# Sheet_1_2025-10-18.net
KiCad netlist of a schematic drawn in Altium Designer
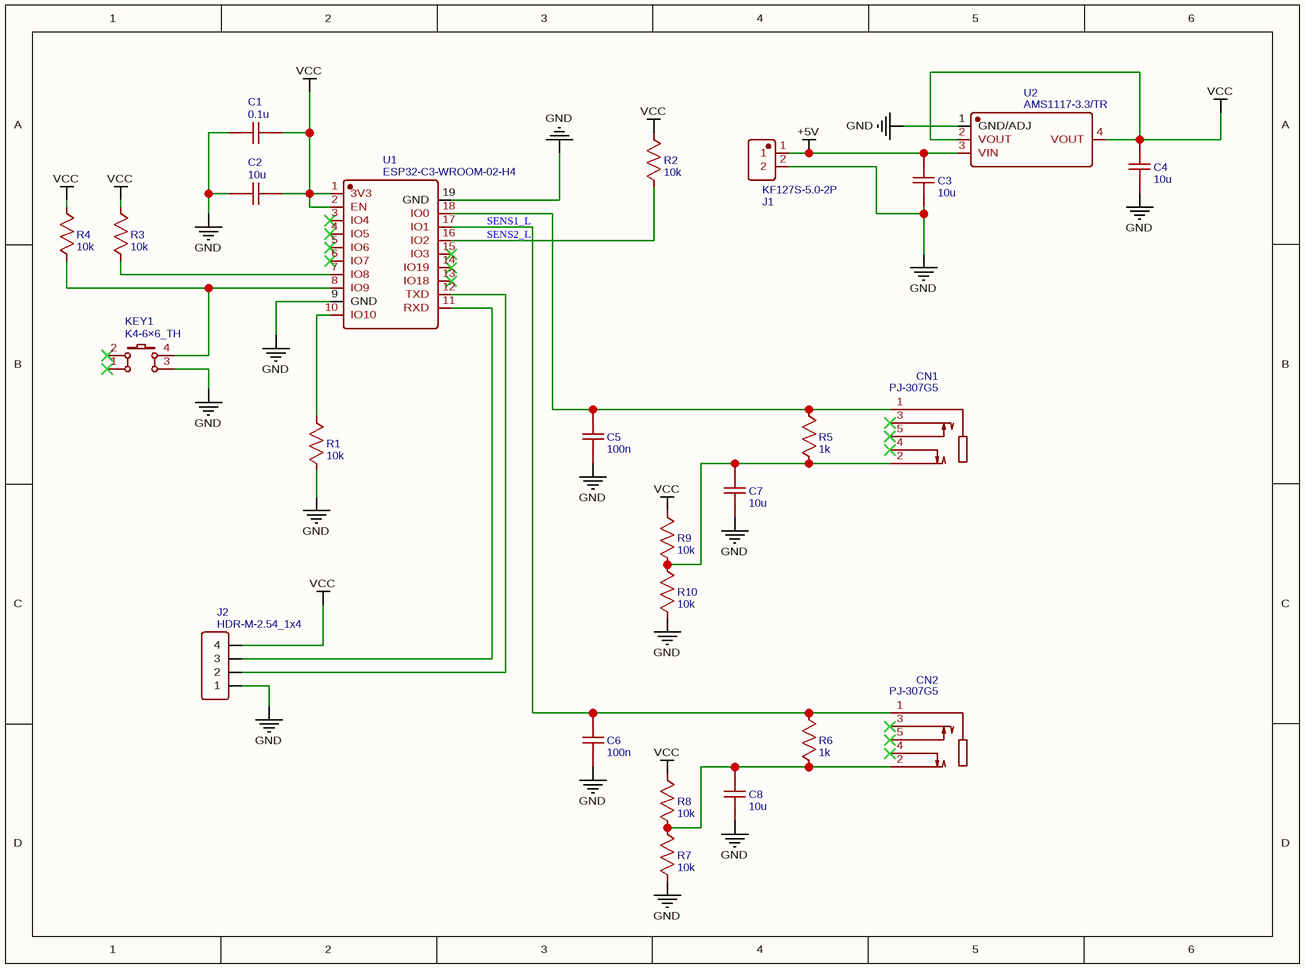
[diagram p0: Sheet_1_2025-10-18.schdoc]

(export (version "E")
  (design (tool "Eeschema 10.0.6"))
  (components
    (comp (ref "C1")
      (value "0.1u")
      (fields (field (name "CONTRIBUTOR") "LCEDA_Lib"))
      (libsource (lib "altium-import") (part "root_0_0.1u_"))
    )
    (comp (ref "C2")
      (value "10u")
      (fields (field (name "CONTRIBUTOR") "LCEDA_Lib"))
      (libsource (lib "altium-import") (part "root_0_10u_"))
    )
    (comp (ref "C3")
      (value "10u")
      (fields (field (name "CONTRIBUTOR") "LCEDA_Lib"))
      (libsource (lib "altium-import") (part "root_1_10u_"))
    )
    (comp (ref "C4")
      (value "10u")
      (fields (field (name "CONTRIBUTOR") "LCEDA_Lib"))
      (libsource (lib "altium-import") (part "root_1_10u_"))
    )
    (comp (ref "C5")
      (value "100n")
      (fields (field (name "CONTRIBUTOR") "LCEDA_Lib"))
      (libsource (lib "altium-import") (part "root_1_100n_"))
    )
    (comp (ref "C6")
      (value "100n")
      (fields (field (name "CONTRIBUTOR") "LCEDA_Lib"))
      (libsource (lib "altium-import") (part "root_1_100n_"))
    )
    (comp (ref "C7")
      (value "10u")
      (fields (field (name "CONTRIBUTOR") "LCEDA_Lib"))
      (libsource (lib "altium-import") (part "root_1_10u_"))
    )
    (comp (ref "C8")
      (value "10u")
      (fields (field (name "CONTRIBUTOR") "LCEDA_Lib"))
      (libsource (lib "altium-import") (part "root_1_10u_"))
    )
    (comp (ref "CN1")
      (value "PJ-307G5")
      (fields (field (name "MANUFACTURER") "XKB Connectivity(中国星坤)") (field (name "CONTRIBUTOR") "LCSC"))
      (libsource (lib "altium-import") (part "root_0_PJ-307G5_"))
    )
    (comp (ref "CN2")
      (value "PJ-307G5")
      (fields (field (name "MANUFACTURER") "XKB Connectivity(中国星坤)") (field (name "CONTRIBUTOR") "LCSC"))
      (libsource (lib "altium-import") (part "root_0_PJ-307G5_"))
    )
    (comp (ref "J1")
      (value "KF127S-5.0-2P")
      (fields (field (name "MANUFACTURER") "KEFA(科发)") (field (name "CONTRIBUTOR") "lcsc"))
      (libsource (lib "altium-import") (part "root_2_KF127S-5.0-2P_"))
    )
    (comp (ref "J2")
      (value "HDR-M-2.54_1x4")
      (fields (field (name "CONTRIBUTOR") "LCEDA_Lib"))
      (libsource (lib "altium-import") (part "root_2_HDR-M-2.54_1x4_"))
    )
    (comp (ref "KEY1")
      (value "K4-6×6_TH")
      (fields
        (field (name "MANUFACTURER") "韩国韩荣")
        (field (name "MANUFACTURER PART") "K2-1102DP-E4SW-04")
        (field (name "CONTRIBUTOR") "LCEDA_Lib")
      )
      (libsource (lib "altium-import") (part "root_0_K4-6×6_TH_"))
    )
    (comp (ref "R1")
      (value "10k")
      (fields (field (name "CONTRIBUTOR") "LCEDA_Lib"))
      (libsource (lib "altium-import") (part "root_1_10k_"))
    )
    (comp (ref "R2")
      (value "10k")
      (fields (field (name "CONTRIBUTOR") "LCEDA_Lib"))
      (libsource (lib "altium-import") (part "root_1_10k_"))
    )
    (comp (ref "R3")
      (value "10k")
      (fields (field (name "CONTRIBUTOR") "LCEDA_Lib"))
      (libsource (lib "altium-import") (part "root_1_10k_"))
    )
    (comp (ref "R4")
      (value "10k")
      (fields (field (name "CONTRIBUTOR") "LCEDA_Lib"))
      (libsource (lib "altium-import") (part "root_1_10k_"))
    )
    (comp (ref "R5")
      (value "1k")
      (fields (field (name "CONTRIBUTOR") "LCEDA_Lib"))
      (libsource (lib "altium-import") (part "root_1_1k_"))
    )
    (comp (ref "R6")
      (value "1k")
      (fields (field (name "CONTRIBUTOR") "LCEDA_Lib"))
      (libsource (lib "altium-import") (part "root_1_1k_"))
    )
    (comp (ref "R7")
      (value "10k")
      (fields (field (name "CONTRIBUTOR") "LCEDA_Lib"))
      (libsource (lib "altium-import") (part "root_1_10k_"))
    )
    (comp (ref "R8")
      (value "10k")
      (fields (field (name "CONTRIBUTOR") "LCEDA_Lib"))
      (libsource (lib "altium-import") (part "root_1_10k_"))
    )
    (comp (ref "R9")
      (value "10k")
      (fields (field (name "CONTRIBUTOR") "LCEDA_Lib"))
      (libsource (lib "altium-import") (part "root_1_10k_"))
    )
    (comp (ref "R10")
      (value "10k")
      (fields (field (name "CONTRIBUTOR") "LCEDA_Lib"))
      (libsource (lib "altium-import") (part "root_1_10k_"))
    )
    (comp (ref "U1")
      (value "ESP32-C3-WROOM-02-H4")
      (fields (field (name "MANUFACTURER") "ESPRESSIF(乐鑫)") (field (name "CONTRIBUTOR") "LCSC"))
      (libsource (lib "altium-import") (part "root_0_ESP32-C3-WROOM-02-H4_"))
    )
    (comp (ref "U2")
      (value "AMS1117-3.3/TR")
      (fields (field (name "MANUFACTURER") "HGSEMI(华冠)") (field (name "CONTRIBUTOR") "lcsc"))
      (libsource (lib "altium-import") (part "root_0_AMS1117-3.3/TR_"))
    )
  )
  (nets
    (net (code "1") (name "+5V") (class "Default")
      (node (ref "C3") (pin "2") (pinfunction "2_2") (pintype "passive"))
      (node (ref "J1") (pin "1") (pinfunction "1_1") (pintype "passive"))
      (node (ref "U2") (pin "3") (pinfunction "VIN_3") (pintype "passive"))
    )
    (net (code "2") (name "/SENS1_L") (class "Default")
      (node (ref "C5") (pin "2") (pinfunction "2_2") (pintype "passive"))
      (node (ref "CN1") (pin "1") (pinfunction "1_1") (pintype "passive"))
      (node (ref "R5") (pin "2") (pinfunction "2_2") (pintype "passive"))
      (node (ref "U1") (pin "18") (pinfunction "IO0_18") (pintype "passive"))
    )
    (net (code "3") (name "/SENS2_L") (class "Default")
      (node (ref "C6") (pin "2") (pinfunction "2_2") (pintype "passive"))
      (node (ref "CN2") (pin "1") (pinfunction "1_1") (pintype "passive"))
      (node (ref "R6") (pin "2") (pinfunction "2_2") (pintype "passive"))
      (node (ref "U1") (pin "17") (pinfunction "IO1_17") (pintype "passive"))
    )
    (net (code "4") (name "GND") (class "Default")
      (node (ref "C1") (pin "1") (pinfunction "1_1") (pintype "passive"))
      (node (ref "C2") (pin "1") (pinfunction "1_1") (pintype "passive"))
      (node (ref "C3") (pin "1") (pinfunction "1_1") (pintype "passive"))
      (node (ref "C4") (pin "1") (pinfunction "1_1") (pintype "passive"))
      (node (ref "C5") (pin "1") (pinfunction "1_1") (pintype "passive"))
      (node (ref "C6") (pin "1") (pinfunction "1_1") (pintype "passive"))
      (node (ref "C7") (pin "1") (pinfunction "1_1") (pintype "passive"))
      (node (ref "C8") (pin "1") (pinfunction "1_1") (pintype "passive"))
      (node (ref "J1") (pin "2") (pinfunction "2_2") (pintype "passive"))
      (node (ref "J2") (pin "1") (pinfunction "1_1") (pintype "passive"))
      (node (ref "KEY1") (pin "3") (pinfunction "3_3") (pintype "passive"))
      (node (ref "R1") (pin "1") (pinfunction "1_1") (pintype "passive"))
      (node (ref "R10") (pin "1") (pinfunction "1_1") (pintype "passive"))
      (node (ref "R7") (pin "1") (pinfunction "1_1") (pintype "passive"))
      (node (ref "U1") (pin "19") (pinfunction "GND_19") (pintype "passive"))
      (node (ref "U1") (pin "9") (pinfunction "GND_9") (pintype "passive"))
      (node (ref "U2") (pin "1") (pinfunction "GND/ADJ_1") (pintype "passive"))
    )
    (net (code "5") (name "Net-(C7-Pad2)") (class "Default")
      (node (ref "C7") (pin "2") (pinfunction "2_2") (pintype "passive"))
      (node (ref "CN1") (pin "2") (pinfunction "2_2") (pintype "passive"))
      (node (ref "R10") (pin "2") (pinfunction "2_2") (pintype "passive"))
      (node (ref "R5") (pin "1") (pinfunction "1_1") (pintype "passive"))
      (node (ref "R9") (pin "1") (pinfunction "1_1") (pintype "passive"))
    )
    (net (code "6") (name "Net-(C8-Pad2)") (class "Default")
      (node (ref "C8") (pin "2") (pinfunction "2_2") (pintype "passive"))
      (node (ref "CN2") (pin "2") (pinfunction "2_2") (pintype "passive"))
      (node (ref "R6") (pin "1") (pinfunction "1_1") (pintype "passive"))
      (node (ref "R7") (pin "2") (pinfunction "2_2") (pintype "passive"))
      (node (ref "R8") (pin "1") (pinfunction "1_1") (pintype "passive"))
    )
    (net (code "7") (name "Net-(U1-IO2)") (class "Default")
      (node (ref "R2") (pin "1") (pinfunction "1_1") (pintype "passive"))
      (node (ref "U1") (pin "16") (pinfunction "IO2_16") (pintype "passive"))
    )
    (net (code "8") (name "Net-(U1-IO8)") (class "Default")
      (node (ref "R3") (pin "1") (pinfunction "1_1") (pintype "passive"))
      (node (ref "U1") (pin "7") (pinfunction "IO8_7") (pintype "passive"))
    )
    (net (code "9") (name "Net-(U1-IO9)") (class "Default")
      (node (ref "KEY1") (pin "4") (pinfunction "4_4") (pintype "passive"))
      (node (ref "R4") (pin "1") (pinfunction "1_1") (pintype "passive"))
      (node (ref "U1") (pin "8") (pinfunction "IO9_8") (pintype "passive"))
    )
    (net (code "10") (name "Net-(U1-IO10)") (class "Default")
      (node (ref "R1") (pin "2") (pinfunction "2_2") (pintype "passive"))
      (node (ref "U1") (pin "10") (pinfunction "IO10_10") (pintype "passive"))
    )
    (net (code "11") (name "Net-(U1-RXD)") (class "Default")
      (node (ref "J2") (pin "3") (pinfunction "3_3") (pintype "passive"))
      (node (ref "U1") (pin "11") (pinfunction "RXD_11") (pintype "passive"))
    )
    (net (code "12") (name "Net-(U1-TXD)") (class "Default")
      (node (ref "J2") (pin "2") (pinfunction "2_2") (pintype "passive"))
      (node (ref "U1") (pin "12") (pinfunction "TXD_12") (pintype "passive"))
    )
    (net (code "13") (name "VCC") (class "Default")
      (node (ref "C1") (pin "2") (pinfunction "2_2") (pintype "passive"))
      (node (ref "C2") (pin "2") (pinfunction "2_2") (pintype "passive"))
      (node (ref "C4") (pin "2") (pinfunction "2_2") (pintype "passive"))
      (node (ref "J2") (pin "4") (pinfunction "4_4") (pintype "passive"))
      (node (ref "R2") (pin "2") (pinfunction "2_2") (pintype "passive"))
      (node (ref "R3") (pin "2") (pinfunction "2_2") (pintype "passive"))
      (node (ref "R4") (pin "2") (pinfunction "2_2") (pintype "passive"))
      (node (ref "R8") (pin "2") (pinfunction "2_2") (pintype "passive"))
      (node (ref "R9") (pin "2") (pinfunction "2_2") (pintype "passive"))
      (node (ref "U1") (pin "1") (pinfunction "3V3_1") (pintype "passive"))
      (node (ref "U1") (pin "2") (pinfunction "EN_2") (pintype "passive"))
      (node (ref "U2") (pin "2") (pinfunction "VOUT_2") (pintype "passive"))
      (node (ref "U2") (pin "4") (pinfunction "VOUT_4") (pintype "passive"))
    )
    (net (code "14") (name "unconnected-(CN1-Pad3)") (class "Default")
      (node (ref "CN1") (pin "3") (pinfunction "3_3") (pintype "passive+no_connect"))
    )
    (net (code "15") (name "unconnected-(CN1-Pad4)") (class "Default")
      (node (ref "CN1") (pin "4") (pinfunction "4_4") (pintype "passive+no_connect"))
    )
    (net (code "16") (name "unconnected-(CN1-Pad5)") (class "Default")
      (node (ref "CN1") (pin "5") (pinfunction "5_5") (pintype "passive+no_connect"))
    )
    (net (code "17") (name "unconnected-(CN2-Pad3)") (class "Default")
      (node (ref "CN2") (pin "3") (pinfunction "3_3") (pintype "passive+no_connect"))
    )
    (net (code "18") (name "unconnected-(CN2-Pad4)") (class "Default")
      (node (ref "CN2") (pin "4") (pinfunction "4_4") (pintype "passive+no_connect"))
    )
    (net (code "19") (name "unconnected-(CN2-Pad5)") (class "Default")
      (node (ref "CN2") (pin "5") (pinfunction "5_5") (pintype "passive+no_connect"))
    )
    (net (code "20") (name "unconnected-(KEY1-Pad1)") (class "Default")
      (node (ref "KEY1") (pin "1") (pinfunction "1_1") (pintype "passive+no_connect"))
    )
    (net (code "21") (name "unconnected-(KEY1-Pad2)") (class "Default")
      (node (ref "KEY1") (pin "2") (pinfunction "2_2") (pintype "passive+no_connect"))
    )
    (net (code "22") (name "unconnected-(U1-IO3-Pad15)") (class "Default")
      (node (ref "U1") (pin "15") (pinfunction "IO3_15") (pintype "passive+no_connect"))
    )
    (net (code "23") (name "unconnected-(U1-IO4-Pad3)") (class "Default")
      (node (ref "U1") (pin "3") (pinfunction "IO4_3") (pintype "passive+no_connect"))
    )
    (net (code "24") (name "unconnected-(U1-IO5-Pad4)") (class "Default")
      (node (ref "U1") (pin "4") (pinfunction "IO5_4") (pintype "passive+no_connect"))
    )
    (net (code "25") (name "unconnected-(U1-IO6-Pad5)") (class "Default")
      (node (ref "U1") (pin "5") (pinfunction "IO6_5") (pintype "passive+no_connect"))
    )
    (net (code "26") (name "unconnected-(U1-IO7-Pad6)") (class "Default")
      (node (ref "U1") (pin "6") (pinfunction "IO7_6") (pintype "passive+no_connect"))
    )
    (net (code "27") (name "unconnected-(U1-IO18-Pad13)") (class "Default")
      (node (ref "U1") (pin "13") (pinfunction "IO18_13") (pintype "passive+no_connect"))
    )
    (net (code "28") (name "unconnected-(U1-IO19-Pad14)") (class "Default")
      (node (ref "U1") (pin "14") (pinfunction "IO19_14") (pintype "passive+no_connect"))
    )
  )
)
